# adc121c027.net
KiCad netlist of a schematic drawn in EAGLE
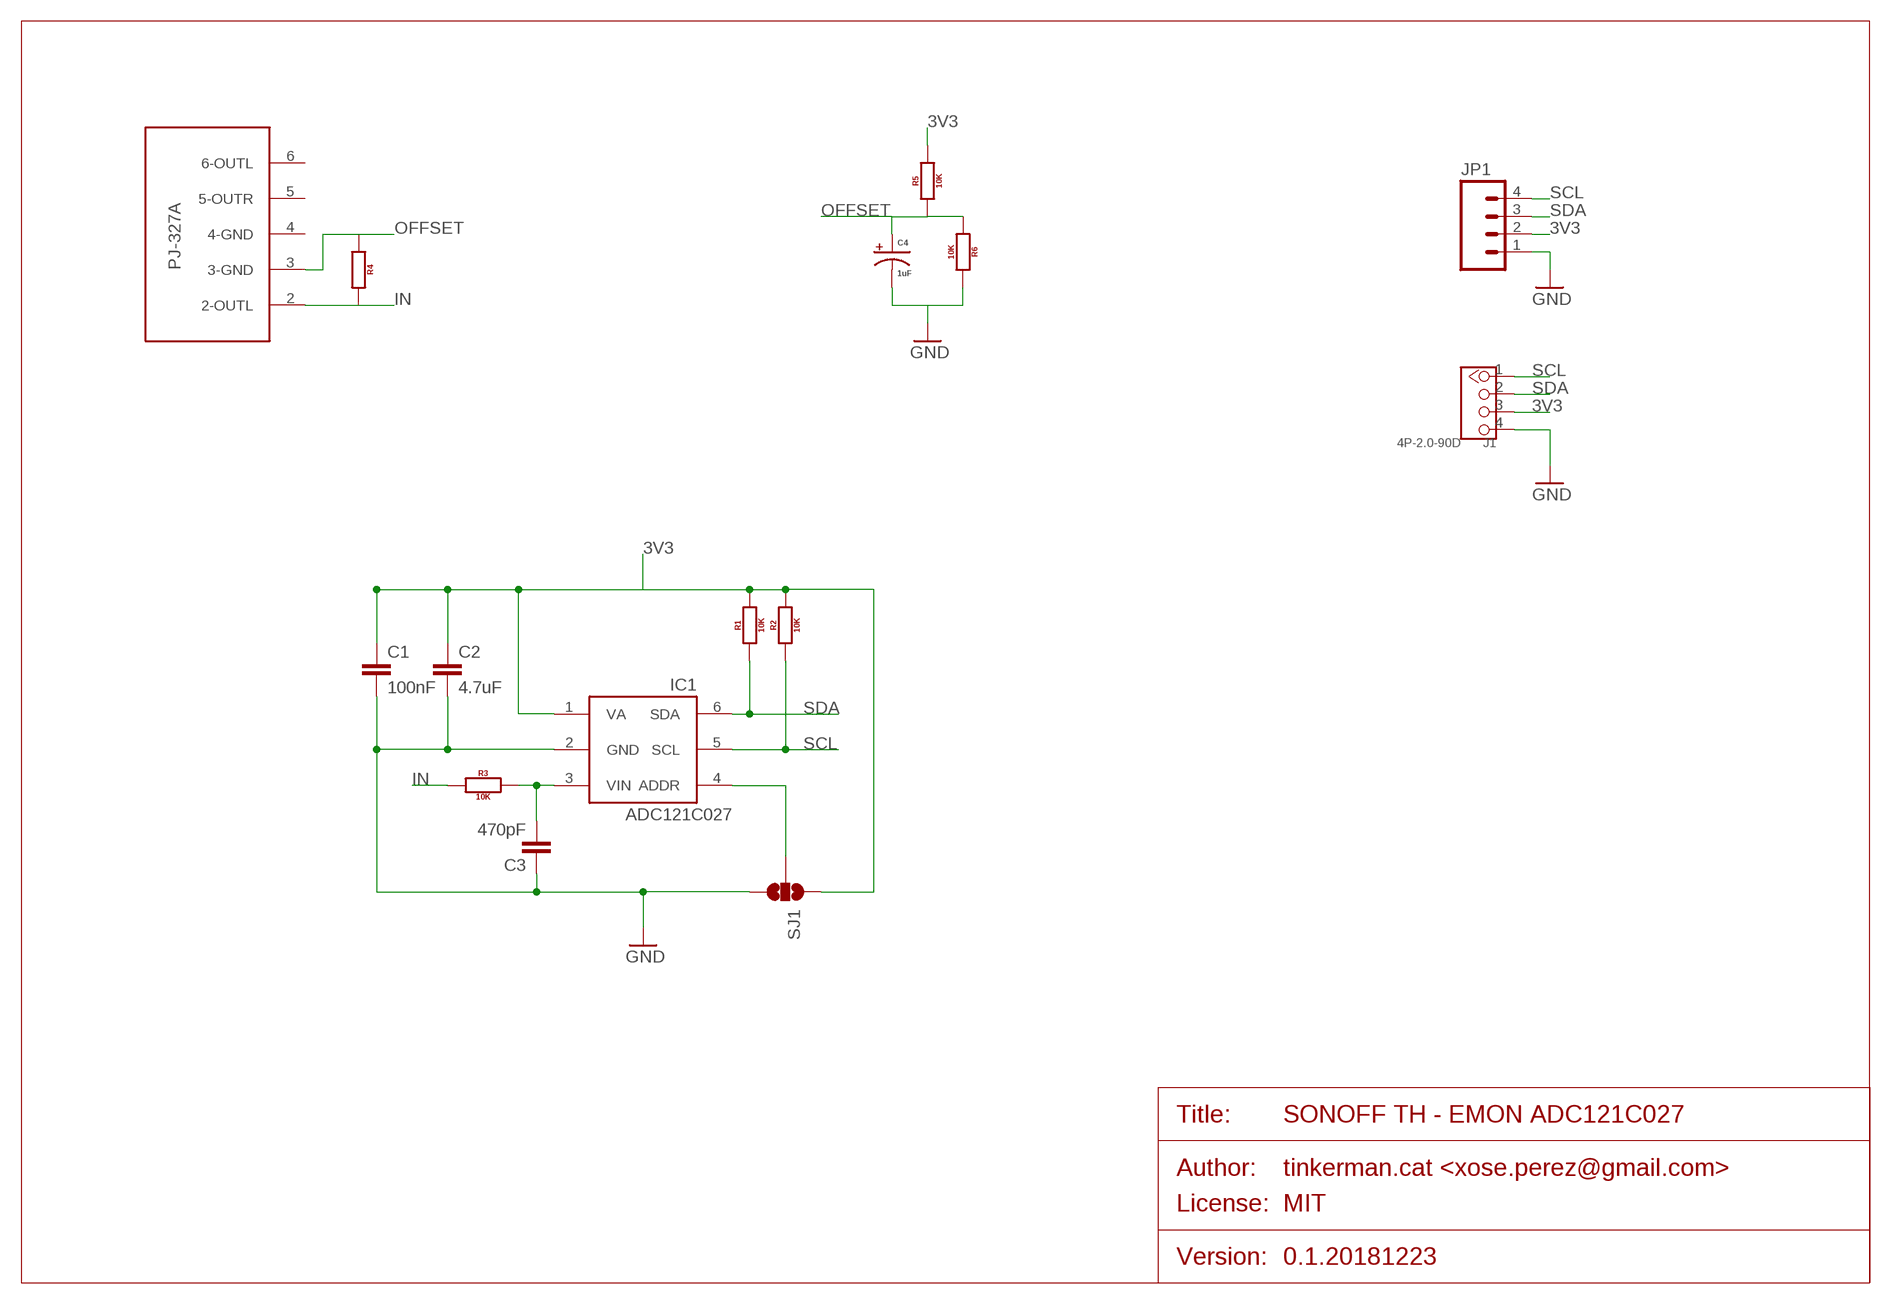
[diagram p0: schematic, sheet 1]

(export (version "E")
  (design (tool "Eeschema 10.0.6"))
  (components
    (comp (ref "C1")
      (value "100nF")
      (footprint "eagle-import:0805")
      (libsource (lib "eagle-import") (part "C-EU0805"))
    )
    (comp (ref "C2")
      (value "4.7uF")
      (footprint "eagle-import:0805")
      (libsource (lib "eagle-import") (part "C-EU0805"))
    )
    (comp (ref "C3")
      (value "470pF")
      (footprint "eagle-import:0805")
      (libsource (lib "eagle-import") (part "C-EU0805"))
    )
    (comp (ref "C4")
      (value "1uF")
      (footprint "eagle-import:PANASONIC_C")
      (libsource (lib "eagle-import") (part "CAP_POLC"))
    )
    (comp (ref "CURR1")
      (value "PJ-327A")
      (footprint "eagle-import:PJ-327A")
      (libsource (lib "eagle-import") (part "PJ-327A"))
    )
    (comp (ref "IC1")
      (value "ADC121C027")
      (footprint "eagle-import:SOT23-6")
      (libsource (lib "eagle-import") (part "ADC121C027"))
    )
    (comp (ref "J1")
      (value "4P-2.0-90D")
      (footprint "eagle-import:HW4-2.0-90D")
      (libsource (lib "eagle-import") (part "GROVE-CONNECTOR-DIP-90D(4P-2.0)"))
    )
    (comp (ref "JP1")
      (value "M04PTH")
      (footprint "eagle-import:1X04")
      (libsource (lib "eagle-import") (part "M04PTH"))
    )
    (comp (ref "R1")
      (value "10K")
      (footprint "eagle-import:0805")
      (libsource (lib "eagle-import") (part "RESISTOR0805"))
    )
    (comp (ref "R2")
      (value "10K")
      (footprint "eagle-import:0805")
      (libsource (lib "eagle-import") (part "RESISTOR0805"))
    )
    (comp (ref "R3")
      (value "10K")
      (footprint "eagle-import:0805")
      (libsource (lib "eagle-import") (part "RESISTOR0805"))
    )
    (comp (ref "R4")
      (value "RESISTOR0805")
      (footprint "eagle-import:0805")
      (libsource (lib "eagle-import") (part "RESISTOR0805"))
    )
    (comp (ref "R5")
      (value "10K")
      (footprint "eagle-import:0805")
      (libsource (lib "eagle-import") (part "RESISTOR0805"))
    )
    (comp (ref "R6")
      (value "10K")
      (footprint "eagle-import:0805")
      (libsource (lib "eagle-import") (part "RESISTOR0805"))
    )
    (comp (ref "SJ1")
      (value "SOLDERJUMPER_2WAYS")
      (footprint "eagle-import:SJ_3")
      (libsource (lib "eagle-import") (part "SOLDERJUMPER_2WAYS"))
    )
  )
  (nets
    (net (code "1") (name "/3V3") (class "Default")
      (node (ref "C1") (pin "1") (pinfunction "1_1") (pintype "passive"))
      (node (ref "C2") (pin "1") (pinfunction "1_1") (pintype "passive"))
      (node (ref "IC1") (pin "1") (pinfunction "VA_1") (pintype "power_in"))
      (node (ref "J1") (pin "3") (pinfunction "3_3") (pintype "bidirectional"))
      (node (ref "JP1") (pin "2") (pinfunction "2_2") (pintype "passive"))
      (node (ref "R1") (pin "2") (pinfunction "2_2") (pintype "passive"))
      (node (ref "R2") (pin "2") (pinfunction "2_2") (pintype "passive"))
      (node (ref "R5") (pin "2") (pinfunction "2_2") (pintype "passive"))
      (node (ref "SJ1") (pin "1") (pinfunction "1_1") (pintype "passive"))
    )
    (net (code "2") (name "/IN") (class "Default")
      (node (ref "CURR1") (pin "2") (pinfunction "2-OUTL_2") (pintype "bidirectional"))
      (node (ref "R3") (pin "1") (pinfunction "1_1") (pintype "passive"))
      (node (ref "R4") (pin "2") (pinfunction "2_2") (pintype "passive"))
    )
    (net (code "3") (name "/OFFSET") (class "Default")
      (node (ref "C4") (pin "+") (pinfunction "+_+") (pintype "passive"))
      (node (ref "CURR1") (pin "3") (pinfunction "3-GND_3") (pintype "bidirectional"))
      (node (ref "R4") (pin "1") (pinfunction "1_1") (pintype "passive"))
      (node (ref "R5") (pin "1") (pinfunction "1_1") (pintype "passive"))
      (node (ref "R6") (pin "1") (pinfunction "1_1") (pintype "passive"))
    )
    (net (code "4") (name "/SCL") (class "Default")
      (node (ref "IC1") (pin "5") (pinfunction "SCL_5") (pintype "bidirectional"))
      (node (ref "J1") (pin "1") (pinfunction "1_1") (pintype "bidirectional"))
      (node (ref "JP1") (pin "4") (pinfunction "4_4") (pintype "passive"))
      (node (ref "R2") (pin "1") (pinfunction "1_1") (pintype "passive"))
    )
    (net (code "5") (name "/SDA") (class "Default")
      (node (ref "IC1") (pin "6") (pinfunction "SDA_6") (pintype "bidirectional"))
      (node (ref "J1") (pin "2") (pinfunction "2_2") (pintype "bidirectional"))
      (node (ref "JP1") (pin "3") (pinfunction "3_3") (pintype "passive"))
      (node (ref "R1") (pin "1") (pinfunction "1_1") (pintype "passive"))
    )
    (net (code "6") (name "GND") (class "Default")
      (node (ref "C1") (pin "2") (pinfunction "2_2") (pintype "passive"))
      (node (ref "C2") (pin "2") (pinfunction "2_2") (pintype "passive"))
      (node (ref "C3") (pin "1") (pinfunction "1_1") (pintype "passive"))
      (node (ref "C4") (pin "-") (pinfunction "-_-") (pintype "passive"))
      (node (ref "IC1") (pin "2") (pinfunction "GND_2") (pintype "power_in"))
      (node (ref "J1") (pin "4") (pinfunction "4_4") (pintype "bidirectional"))
      (node (ref "JP1") (pin "1") (pinfunction "1_1") (pintype "passive"))
      (node (ref "R6") (pin "2") (pinfunction "2_2") (pintype "passive"))
      (node (ref "SJ1") (pin "3") (pinfunction "3_3") (pintype "passive"))
    )
    (net (code "7") (name "Net-(IC1-ADDR)") (class "Default")
      (node (ref "IC1") (pin "4") (pinfunction "ADDR_4") (pintype "bidirectional"))
      (node (ref "SJ1") (pin "2") (pinfunction "2_2") (pintype "passive"))
    )
    (net (code "8") (name "Net-(IC1-VIN)") (class "Default")
      (node (ref "C3") (pin "2") (pinfunction "2_2") (pintype "passive"))
      (node (ref "IC1") (pin "3") (pinfunction "VIN_3") (pintype "input"))
      (node (ref "R3") (pin "2") (pinfunction "2_2") (pintype "passive"))
    )
    (net (code "9") (name "unconnected-(CURR1-4-GND-Pad4)") (class "Default")
      (node (ref "CURR1") (pin "4") (pinfunction "4-GND_4") (pintype "bidirectional"))
    )
    (net (code "10") (name "unconnected-(CURR1-5-OUTR-Pad5)") (class "Default")
      (node (ref "CURR1") (pin "5") (pinfunction "5-OUTR_5") (pintype "bidirectional"))
    )
    (net (code "11") (name "unconnected-(CURR1-6-OUTL-Pad6)") (class "Default")
      (node (ref "CURR1") (pin "6") (pinfunction "6-OUTL_6") (pintype "bidirectional"))
    )
  )
)
